# Sheet5.net
KiCad netlist of a schematic drawn in Altium Designer
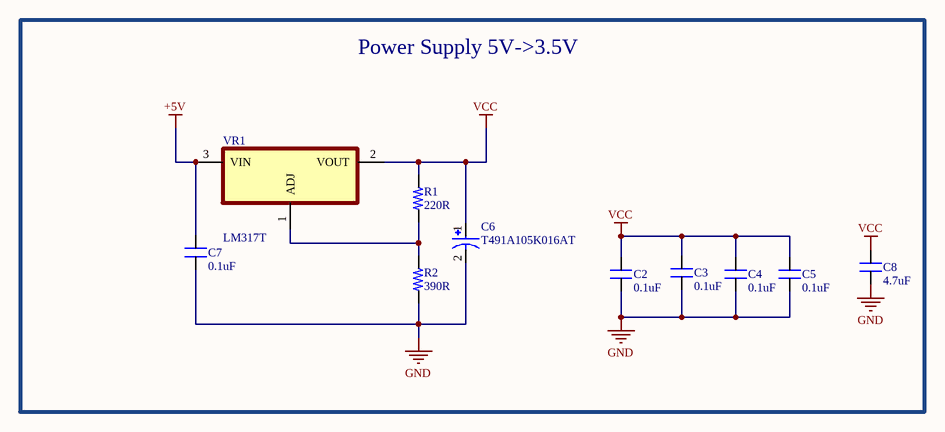
[diagram p0: Sheet5.SchDoc]

(export (version "E")
  (design (tool "Eeschema 10.0.6"))
  (components
    (comp (ref "C2")
      (value "0.1uF")
      (footprint "CAP_0805")
      (description "0.1µF ±5% 50V Ceramic Capacitor X7R 0805 (2012 Metric)")
      (fields
        (field (name "MANUFACTURER") "KEMET")
        (field (name "MANUFACTURING PART NUMBER") "C0805C104J5RACTU")
      )
      (libsource (lib "STM_SCH_LIB") (part "CAP_0.1uF-50V-5%-0805"))
    )
    (comp (ref "C3")
      (value "0.1uF")
      (footprint "CAP_0805")
      (description "0.1µF ±5% 50V Ceramic Capacitor X7R 0805 (2012 Metric)")
      (fields
        (field (name "MANUFACTURER") "KEMET")
        (field (name "MANUFACTURING PART NUMBER") "C0805C104J5RACTU")
      )
      (libsource (lib "STM_SCH_LIB") (part "CAP_0.1uF-50V-5%-0805"))
    )
    (comp (ref "C4")
      (value "0.1uF")
      (footprint "CAP_0805")
      (description "0.1µF ±5% 50V Ceramic Capacitor X7R 0805 (2012 Metric)")
      (fields
        (field (name "MANUFACTURER") "KEMET")
        (field (name "MANUFACTURING PART NUMBER") "C0805C104J5RACTU")
      )
      (libsource (lib "STM_SCH_LIB") (part "CAP_0.1uF-50V-5%-0805"))
    )
    (comp (ref "C5")
      (value "0.1uF")
      (footprint "CAP_0805")
      (description "0.1µF ±5% 50V Ceramic Capacitor X7R 0805 (2012 Metric)")
      (fields
        (field (name "MANUFACTURER") "KEMET")
        (field (name "MANUFACTURING PART NUMBER") "C0805C104J5RACTU")
      )
      (libsource (lib "STM_SCH_LIB") (part "CAP_0.1uF-50V-5%-0805"))
    )
    (comp (ref "C6")
      (value "T491A105K016AT")
      (footprint "CAPMP3216X180N - duplicate")
      (description "1ÂµF Molded Tantalum Capacitors 16V 1206 (3216 Metric) 10Ohm")
      (fields (field (name "MF") "Kemet"))
      (libsource (lib "Power_Plug") (part "T491A105K016AT"))
    )
    (comp (ref "C7")
      (value "0.1uF")
      (footprint "CAP_0805")
      (description "0.1µF ±5% 50V Ceramic Capacitor X7R 0805 (2012 Metric)")
      (fields
        (field (name "MANUFACTURER") "KEMET")
        (field (name "MANUFACTURING PART NUMBER") "C0805C104J5RACTU")
      )
      (libsource (lib "Power_Plug") (part "CAP_0.1uF-50V-5%-0805"))
    )
    (comp (ref "C8")
      (value "4.7uF")
      (footprint "CAP_0805")
      (description "0.1µF ±5% 50V Ceramic Capacitor X7R 0805 (2012 Metric)")
      (fields
        (field (name "MANUFACTURER") "KEMET")
        (field (name "MANUFACTURING PART NUMBER") "C0805C104J5RACTU")
      )
      (libsource (lib "Power_Plug") (part "CAP_4.7uF-50V-5%-0805_1"))
    )
    (comp (ref "R1")
      (value "220R")
      (footprint "RES_0805")
      (description "220 Ohms ±1% 0.125W, 1/8W Chip Resistor 0805 (2012 Metric) Thick Film")
      (fields
        (field (name "MANUFACTURER") "TE Connectivity Passive Product")
        (field (name "MANUFACTURING PART NUMBER") "CRG0805F1K5")
      )
      (libsource (lib "Power_Plug") (part "RES_220R-0.125W-1%-0805_1_1_1"))
    )
    (comp (ref "R2")
      (value "390R")
      (footprint "RES_0805")
      (description "390Ohms ±1% 0.125W, 1/8W Chip Resistor 0805 (2012 Metric) Thick Film")
      (fields
        (field (name "MANUFACTURER") "TE Connectivity Passive Product")
        (field (name "MANUFACTURING PART NUMBER") "CRG0805F1K5")
      )
      (libsource (lib "Power_Plug") (part "RES_390R-0.125W-1%-0805_1_1"))
    )
    (comp (ref "VR1")
      (value "LM317T")
      (footprint "TO254P1054X470X1955-3")
      (description "1.5-A, 40-V, adjustable linear voltage regulator 3-TO-220")
      (fields (field (name "MF") "Texas Instruments"))
      (libsource (lib "Power_Plug") (part "LM317T"))
    )
  )
  (nets
    (net (code "1") (name "+5V") (class "Default")
      (node (ref "C7") (pin "2") (pinfunction "2_2") (pintype "passive"))
      (node (ref "VR1") (pin "3") (pinfunction "VIN_3") (pintype "passive"))
    )
    (net (code "2") (name "GND") (class "Default")
      (node (ref "C2") (pin "1") (pinfunction "1_1") (pintype "passive"))
      (node (ref "C3") (pin "1") (pinfunction "1_1") (pintype "passive"))
      (node (ref "C4") (pin "1") (pinfunction "1_1") (pintype "passive"))
      (node (ref "C5") (pin "1") (pinfunction "1_1") (pintype "passive"))
      (node (ref "C6") (pin "2") (pinfunction "2_2") (pintype "passive"))
      (node (ref "C7") (pin "1") (pinfunction "1_1") (pintype "passive"))
      (node (ref "C8") (pin "1") (pinfunction "1_1") (pintype "passive"))
      (node (ref "R2") (pin "1") (pinfunction "1_1") (pintype "passive"))
    )
    (net (code "3") (name "Net-(VR1-ADJ)") (class "Default")
      (node (ref "R1") (pin "1") (pinfunction "1_1") (pintype "passive"))
      (node (ref "R2") (pin "2") (pinfunction "2_2") (pintype "passive"))
      (node (ref "VR1") (pin "1") (pinfunction "ADJ_1") (pintype "passive"))
    )
    (net (code "4") (name "VCC") (class "Default")
      (node (ref "C2") (pin "2") (pinfunction "2_2") (pintype "passive"))
      (node (ref "C3") (pin "2") (pinfunction "2_2") (pintype "passive"))
      (node (ref "C4") (pin "2") (pinfunction "2_2") (pintype "passive"))
      (node (ref "C5") (pin "2") (pinfunction "2_2") (pintype "passive"))
      (node (ref "C6") (pin "1") (pinfunction "1_1") (pintype "passive"))
      (node (ref "C8") (pin "2") (pinfunction "2_2") (pintype "passive"))
      (node (ref "R1") (pin "2") (pinfunction "2_2") (pintype "passive"))
      (node (ref "VR1") (pin "2") (pinfunction "VOUT_2") (pintype "passive"))
    )
  )
)
